# LED_PD_AB_WH_3000149.net
KiCad netlist of a schematic drawn in Altium Designer
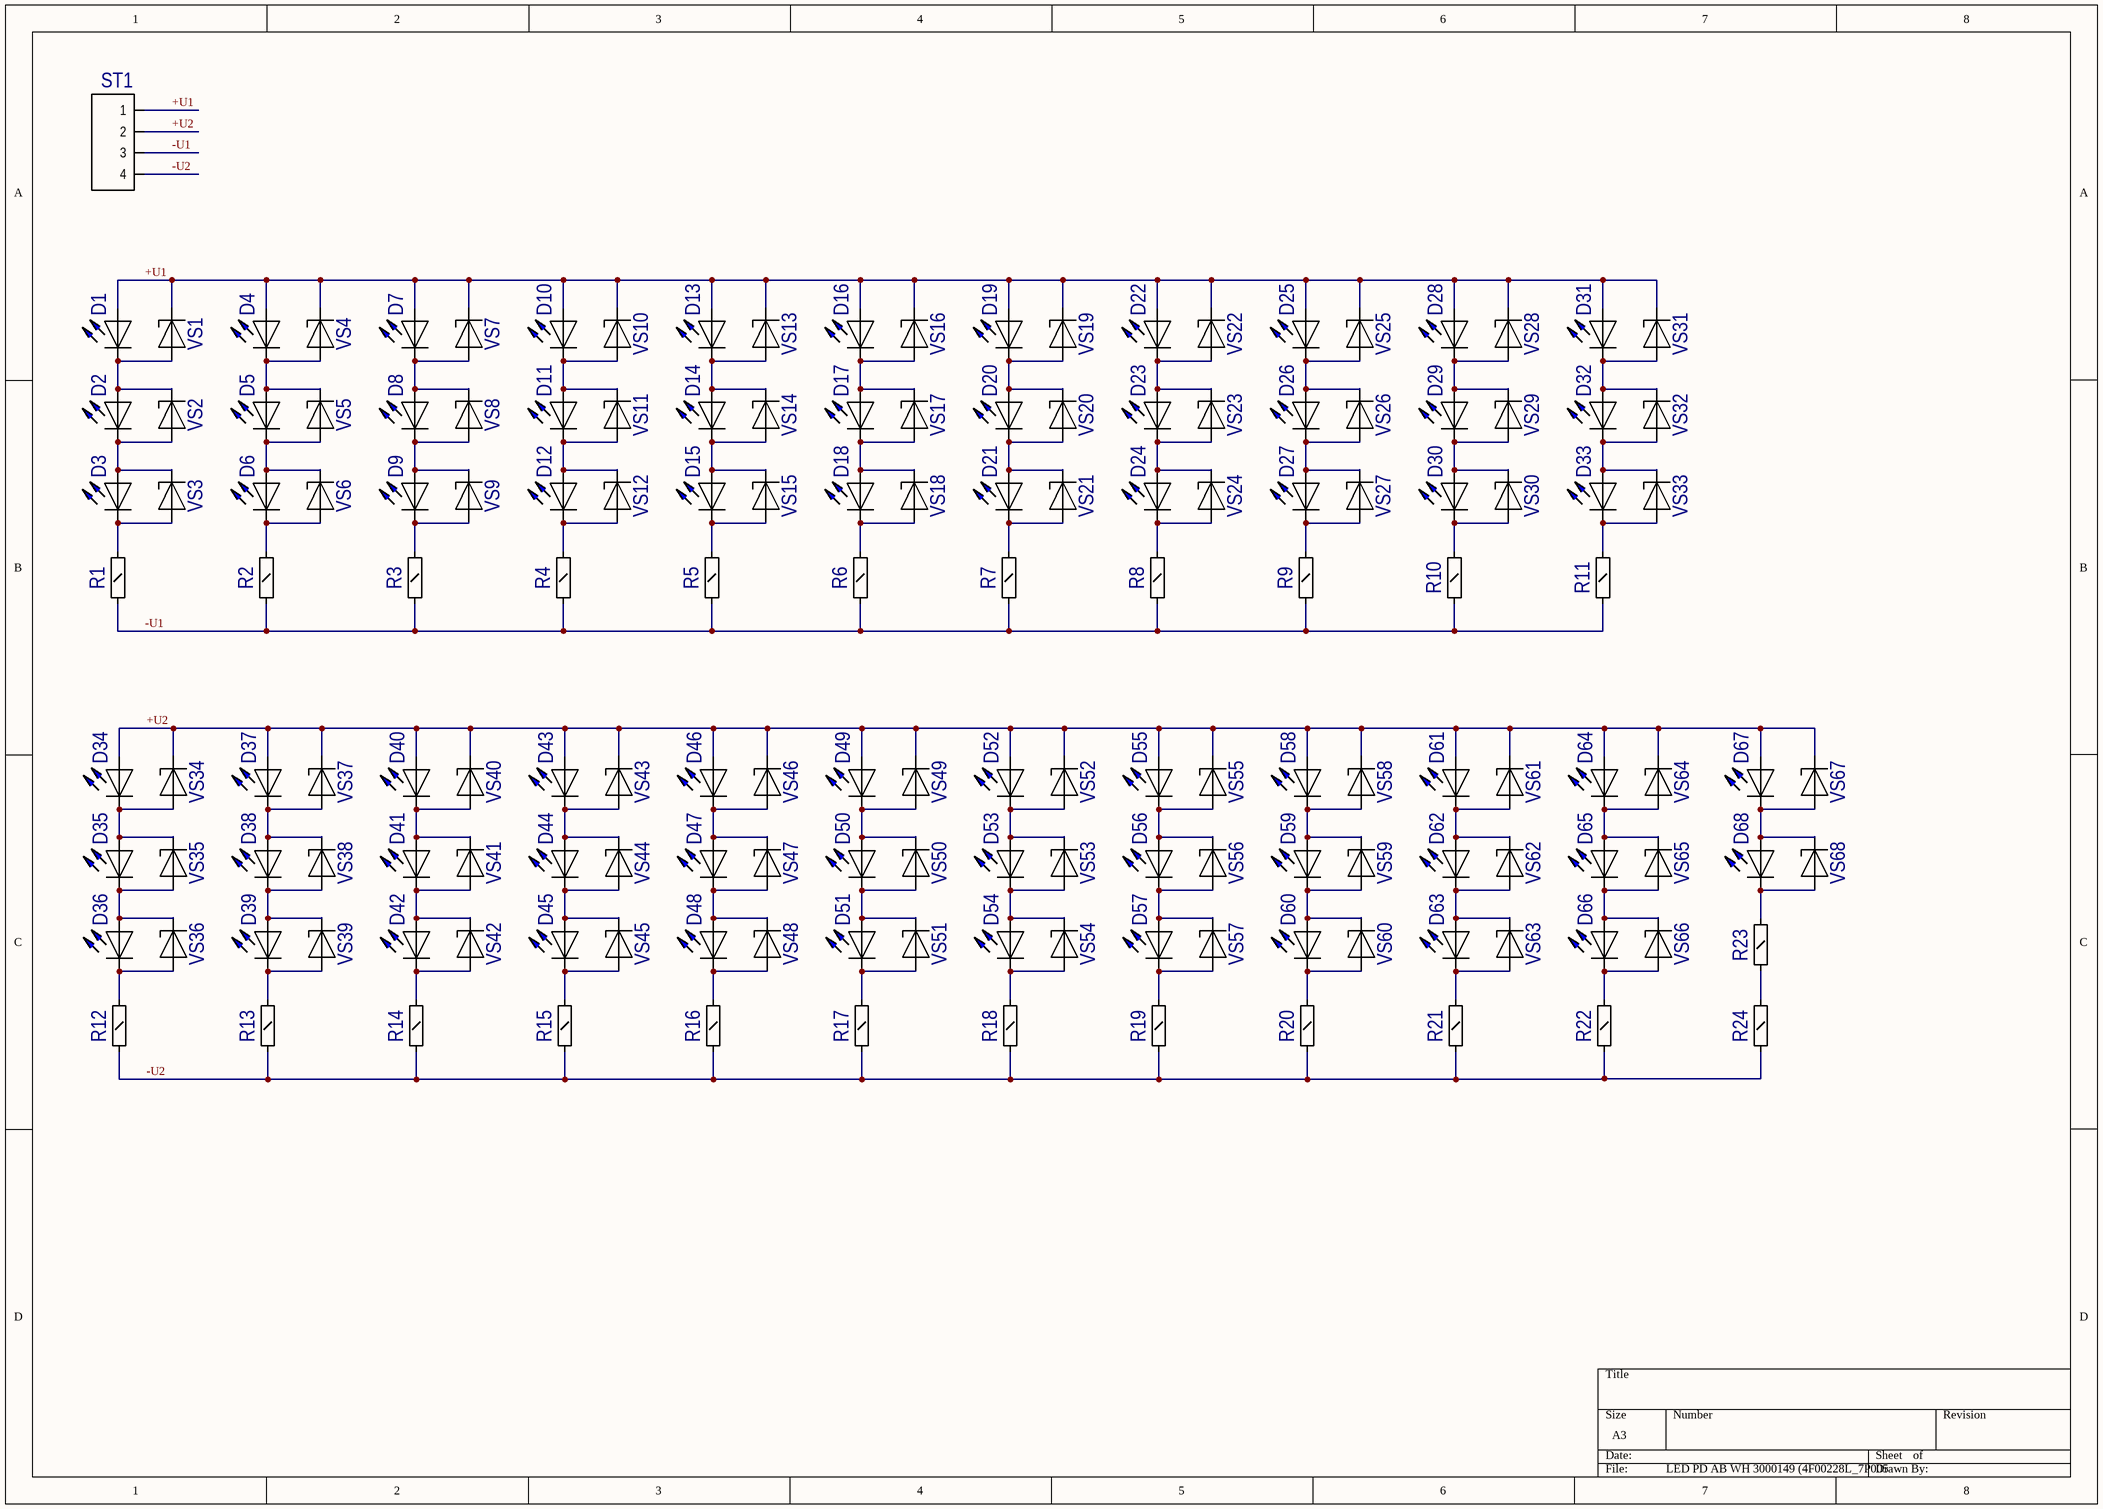
[diagram p0: LED PD AB WH 3000149 (4F00228L_7P00501A)_sch.SchDoc]

(export (version "E")
  (design (tool "Eeschema 10.0.6"))
  (components
    (comp (ref "D1")
      (value "LT_T66G")
      (footprint "T66G")
      (description "{Description}")
      (libsource (lib "LED PD GTL WH 3000148 (4F00222L_7P00492A)") (part "LT_T66G"))
    )
    (comp (ref "D2")
      (value "LT_T66G")
      (footprint "T66G")
      (description "{Description}")
      (libsource (lib "LED PD GTL WH 3000148 (4F00222L_7P00492A)") (part "LT_T66G"))
    )
    (comp (ref "D3")
      (value "LT_T66G")
      (footprint "T66G")
      (description "{Description}")
      (libsource (lib "LED PD GTL WH 3000148 (4F00222L_7P00492A)") (part "LT_T66G"))
    )
    (comp (ref "D4")
      (value "LT_T66G")
      (footprint "T66G")
      (description "{Description}")
      (libsource (lib "LED PD GTL WH 3000148 (4F00222L_7P00492A)") (part "LT_T66G"))
    )
    (comp (ref "D5")
      (value "LT_T66G")
      (footprint "T66G")
      (description "{Description}")
      (libsource (lib "LED PD GTL WH 3000148 (4F00222L_7P00492A)") (part "LT_T66G"))
    )
    (comp (ref "D6")
      (value "LT_T66G")
      (footprint "T66G")
      (description "{Description}")
      (libsource (lib "LED PD GTL WH 3000148 (4F00222L_7P00492A)") (part "LT_T66G"))
    )
    (comp (ref "D7")
      (value "LT_T66G")
      (footprint "T66G")
      (description "{Description}")
      (libsource (lib "LED PD GTL WH 3000148 (4F00222L_7P00492A)") (part "LT_T66G"))
    )
    (comp (ref "D8")
      (value "LT_T66G")
      (footprint "T66G")
      (description "{Description}")
      (libsource (lib "LED PD GTL WH 3000148 (4F00222L_7P00492A)") (part "LT_T66G"))
    )
    (comp (ref "D9")
      (value "LT_T66G")
      (footprint "T66G")
      (description "{Description}")
      (libsource (lib "LED PD GTL WH 3000148 (4F00222L_7P00492A)") (part "LT_T66G"))
    )
    (comp (ref "D10")
      (value "LT_T66G")
      (footprint "T66G")
      (description "{Description}")
      (libsource (lib "LED PD GTL WH 3000148 (4F00222L_7P00492A)") (part "LT_T66G"))
    )
    (comp (ref "D11")
      (value "LT_T66G")
      (footprint "T66G")
      (description "{Description}")
      (libsource (lib "LED PD GTL WH 3000148 (4F00222L_7P00492A)") (part "LT_T66G"))
    )
    (comp (ref "D12")
      (value "LT_T66G")
      (footprint "T66G")
      (description "{Description}")
      (libsource (lib "LED PD GTL WH 3000148 (4F00222L_7P00492A)") (part "LT_T66G"))
    )
    (comp (ref "D13")
      (value "LT_T66G")
      (footprint "T66G")
      (description "{Description}")
      (libsource (lib "LED PD GTL WH 3000148 (4F00222L_7P00492A)") (part "LT_T66G"))
    )
    (comp (ref "D14")
      (value "LT_T66G")
      (footprint "T66G")
      (description "{Description}")
      (libsource (lib "LED PD GTL WH 3000148 (4F00222L_7P00492A)") (part "LT_T66G"))
    )
    (comp (ref "D15")
      (value "LT_T66G")
      (footprint "T66G")
      (description "{Description}")
      (libsource (lib "LED PD GTL WH 3000148 (4F00222L_7P00492A)") (part "LT_T66G"))
    )
    (comp (ref "D16")
      (value "LT_T66G")
      (footprint "T66G")
      (description "{Description}")
      (libsource (lib "LED PD GTL WH 3000148 (4F00222L_7P00492A)") (part "LT_T66G"))
    )
    (comp (ref "D17")
      (value "LT_T66G")
      (footprint "T66G")
      (description "{Description}")
      (libsource (lib "LED PD GTL WH 3000148 (4F00222L_7P00492A)") (part "LT_T66G"))
    )
    (comp (ref "D18")
      (value "LT_T66G")
      (footprint "T66G")
      (description "{Description}")
      (libsource (lib "LED PD GTL WH 3000148 (4F00222L_7P00492A)") (part "LT_T66G"))
    )
    (comp (ref "D19")
      (value "LT_T66G")
      (footprint "T66G")
      (description "{Description}")
      (libsource (lib "LED PD GTL WH 3000148 (4F00222L_7P00492A)") (part "LT_T66G"))
    )
    (comp (ref "D20")
      (value "LT_T66G")
      (footprint "T66G")
      (description "{Description}")
      (libsource (lib "LED PD GTL WH 3000148 (4F00222L_7P00492A)") (part "LT_T66G"))
    )
    (comp (ref "D21")
      (value "LT_T66G")
      (footprint "T66G")
      (description "{Description}")
      (libsource (lib "LED PD GTL WH 3000148 (4F00222L_7P00492A)") (part "LT_T66G"))
    )
    (comp (ref "D22")
      (value "LT_T66G")
      (footprint "T66G")
      (description "{Description}")
      (libsource (lib "LED PD GTL WH 3000148 (4F00222L_7P00492A)") (part "LT_T66G"))
    )
    (comp (ref "D23")
      (value "LT_T66G")
      (footprint "T66G")
      (description "{Description}")
      (libsource (lib "LED PD GTL WH 3000148 (4F00222L_7P00492A)") (part "LT_T66G"))
    )
    (comp (ref "D24")
      (value "LT_T66G")
      (footprint "T66G")
      (description "{Description}")
      (libsource (lib "LED PD GTL WH 3000148 (4F00222L_7P00492A)") (part "LT_T66G"))
    )
    (comp (ref "D25")
      (value "LT_T66G")
      (footprint "T66G")
      (description "{Description}")
      (libsource (lib "LED PD GTL WH 3000148 (4F00222L_7P00492A)") (part "LT_T66G"))
    )
    (comp (ref "D26")
      (value "LT_T66G")
      (footprint "T66G")
      (description "{Description}")
      (libsource (lib "LED PD GTL WH 3000148 (4F00222L_7P00492A)") (part "LT_T66G"))
    )
    (comp (ref "D27")
      (value "LT_T66G")
      (footprint "T66G")
      (description "{Description}")
      (libsource (lib "LED PD GTL WH 3000148 (4F00222L_7P00492A)") (part "LT_T66G"))
    )
    (comp (ref "D28")
      (value "LT_T66G")
      (footprint "T66G")
      (description "{Description}")
      (libsource (lib "LED PD GTL WH 3000148 (4F00222L_7P00492A)") (part "LT_T66G"))
    )
    (comp (ref "D29")
      (value "LT_T66G")
      (footprint "T66G")
      (description "{Description}")
      (libsource (lib "LED PD GTL WH 3000148 (4F00222L_7P00492A)") (part "LT_T66G"))
    )
    (comp (ref "D30")
      (value "LT_T66G")
      (footprint "T66G")
      (description "{Description}")
      (libsource (lib "LED PD GTL WH 3000148 (4F00222L_7P00492A)") (part "LT_T66G"))
    )
    (comp (ref "D31")
      (value "LT_T66G")
      (footprint "T66G")
      (description "{Description}")
      (libsource (lib "LED PD GTL WH 3000148 (4F00222L_7P00492A)") (part "LT_T66G"))
    )
    (comp (ref "D32")
      (value "LT_T66G")
      (footprint "T66G")
      (description "{Description}")
      (libsource (lib "LED PD GTL WH 3000148 (4F00222L_7P00492A)") (part "LT_T66G"))
    )
    (comp (ref "D33")
      (value "LT_T66G")
      (footprint "T66G")
      (description "{Description}")
      (libsource (lib "LED PD GTL WH 3000148 (4F00222L_7P00492A)") (part "LT_T66G"))
    )
    (comp (ref "D34")
      (value "LT_T66G")
      (footprint "T66G")
      (description "{Description}")
      (libsource (lib "LED PD GTL WH 3000148 (4F00222L_7P00492A)") (part "LT_T66G"))
    )
    (comp (ref "D35")
      (value "LT_T66G")
      (footprint "T66G")
      (description "{Description}")
      (libsource (lib "LED PD GTL WH 3000148 (4F00222L_7P00492A)") (part "LT_T66G"))
    )
    (comp (ref "D36")
      (value "LT_T66G")
      (footprint "T66G")
      (description "{Description}")
      (libsource (lib "LED PD GTL WH 3000148 (4F00222L_7P00492A)") (part "LT_T66G"))
    )
    (comp (ref "D37")
      (value "LT_T66G")
      (footprint "T66G")
      (description "{Description}")
      (libsource (lib "LED PD GTL WH 3000148 (4F00222L_7P00492A)") (part "LT_T66G"))
    )
    (comp (ref "D38")
      (value "LT_T66G")
      (footprint "T66G")
      (description "{Description}")
      (libsource (lib "LED PD GTL WH 3000148 (4F00222L_7P00492A)") (part "LT_T66G"))
    )
    (comp (ref "D39")
      (value "LT_T66G")
      (footprint "T66G")
      (description "{Description}")
      (libsource (lib "LED PD GTL WH 3000148 (4F00222L_7P00492A)") (part "LT_T66G"))
    )
    (comp (ref "D40")
      (value "LT_T66G")
      (footprint "T66G")
      (description "{Description}")
      (libsource (lib "LED PD GTL WH 3000148 (4F00222L_7P00492A)") (part "LT_T66G"))
    )
    (comp (ref "D41")
      (value "LT_T66G")
      (footprint "T66G")
      (description "{Description}")
      (libsource (lib "LED PD GTL WH 3000148 (4F00222L_7P00492A)") (part "LT_T66G"))
    )
    (comp (ref "D42")
      (value "LT_T66G")
      (footprint "T66G")
      (description "{Description}")
      (libsource (lib "LED PD GTL WH 3000148 (4F00222L_7P00492A)") (part "LT_T66G"))
    )
    (comp (ref "D43")
      (value "LT_T66G")
      (footprint "T66G")
      (description "{Description}")
      (libsource (lib "LED PD GTL WH 3000148 (4F00222L_7P00492A)") (part "LT_T66G"))
    )
    (comp (ref "D44")
      (value "LT_T66G")
      (footprint "T66G")
      (description "{Description}")
      (libsource (lib "LED PD GTL WH 3000148 (4F00222L_7P00492A)") (part "LT_T66G"))
    )
    (comp (ref "D45")
      (value "LT_T66G")
      (footprint "T66G")
      (description "{Description}")
      (libsource (lib "LED PD GTL WH 3000148 (4F00222L_7P00492A)") (part "LT_T66G"))
    )
    (comp (ref "D46")
      (value "LT_T66G")
      (footprint "T66G")
      (description "{Description}")
      (libsource (lib "LED PD GTL WH 3000148 (4F00222L_7P00492A)") (part "LT_T66G"))
    )
    (comp (ref "D47")
      (value "LT_T66G")
      (footprint "T66G")
      (description "{Description}")
      (libsource (lib "LED PD GTL WH 3000148 (4F00222L_7P00492A)") (part "LT_T66G"))
    )
    (comp (ref "D48")
      (value "LT_T66G")
      (footprint "T66G")
      (description "{Description}")
      (libsource (lib "LED PD GTL WH 3000148 (4F00222L_7P00492A)") (part "LT_T66G"))
    )
    (comp (ref "D49")
      (value "LT_T66G")
      (footprint "T66G")
      (description "{Description}")
      (libsource (lib "LED PD GTL WH 3000148 (4F00222L_7P00492A)") (part "LT_T66G"))
    )
    (comp (ref "D50")
      (value "LT_T66G")
      (footprint "T66G")
      (description "{Description}")
      (libsource (lib "LED PD GTL WH 3000148 (4F00222L_7P00492A)") (part "LT_T66G"))
    )
    (comp (ref "D51")
      (value "LT_T66G")
      (footprint "T66G")
      (description "{Description}")
      (libsource (lib "LED PD GTL WH 3000148 (4F00222L_7P00492A)") (part "LT_T66G"))
    )
    (comp (ref "D52")
      (value "LT_T66G")
      (footprint "T66G")
      (description "{Description}")
      (libsource (lib "LED PD GTL WH 3000148 (4F00222L_7P00492A)") (part "LT_T66G"))
    )
    (comp (ref "D53")
      (value "LT_T66G")
      (footprint "T66G")
      (description "{Description}")
      (libsource (lib "LED PD GTL WH 3000148 (4F00222L_7P00492A)") (part "LT_T66G"))
    )
    (comp (ref "D54")
      (value "LT_T66G")
      (footprint "T66G")
      (description "{Description}")
      (libsource (lib "LED PD GTL WH 3000148 (4F00222L_7P00492A)") (part "LT_T66G"))
    )
    (comp (ref "D55")
      (value "LT_T66G")
      (footprint "T66G")
      (description "{Description}")
      (libsource (lib "LED PD GTL WH 3000148 (4F00222L_7P00492A)") (part "LT_T66G"))
    )
    (comp (ref "D56")
      (value "LT_T66G")
      (footprint "T66G")
      (description "{Description}")
      (libsource (lib "LED PD GTL WH 3000148 (4F00222L_7P00492A)") (part "LT_T66G"))
    )
    (comp (ref "D57")
      (value "LT_T66G")
      (footprint "T66G")
      (description "{Description}")
      (libsource (lib "LED PD GTL WH 3000148 (4F00222L_7P00492A)") (part "LT_T66G"))
    )
    (comp (ref "D58")
      (value "LT_T66G")
      (footprint "T66G")
      (description "{Description}")
      (libsource (lib "LED PD GTL WH 3000148 (4F00222L_7P00492A)") (part "LT_T66G"))
    )
    (comp (ref "D59")
      (value "LT_T66G")
      (footprint "T66G")
      (description "{Description}")
      (libsource (lib "LED PD GTL WH 3000148 (4F00222L_7P00492A)") (part "LT_T66G"))
    )
    (comp (ref "D60")
      (value "LT_T66G")
      (footprint "T66G")
      (description "{Description}")
      (libsource (lib "LED PD GTL WH 3000148 (4F00222L_7P00492A)") (part "LT_T66G"))
    )
    (comp (ref "D61")
      (value "LT_T66G")
      (footprint "T66G")
      (description "{Description}")
      (libsource (lib "LED PD GTL WH 3000148 (4F00222L_7P00492A)") (part "LT_T66G"))
    )
    (comp (ref "D62")
      (value "LT_T66G")
      (footprint "T66G")
      (description "{Description}")
      (libsource (lib "LED PD GTL WH 3000148 (4F00222L_7P00492A)") (part "LT_T66G"))
    )
    (comp (ref "D63")
      (value "LT_T66G")
      (footprint "T66G")
      (description "{Description}")
      (libsource (lib "LED PD GTL WH 3000148 (4F00222L_7P00492A)") (part "LT_T66G"))
    )
    (comp (ref "D64")
      (value "LT_T66G")
      (footprint "T66G")
      (description "{Description}")
      (libsource (lib "LED PD GTL WH 3000148 (4F00222L_7P00492A)") (part "LT_T66G"))
    )
    (comp (ref "D65")
      (value "LT_T66G")
      (footprint "T66G")
      (description "{Description}")
      (libsource (lib "LED PD GTL WH 3000148 (4F00222L_7P00492A)") (part "LT_T66G"))
    )
    (comp (ref "D66")
      (value "LT_T66G")
      (footprint "T66G")
      (description "{Description}")
      (libsource (lib "LED PD GTL WH 3000148 (4F00222L_7P00492A)") (part "LT_T66G"))
    )
    (comp (ref "D67")
      (value "LT_T66G")
      (footprint "T66G")
      (description "{Description}")
      (libsource (lib "LED PD GTL WH 3000148 (4F00222L_7P00492A)") (part "LT_T66G"))
    )
    (comp (ref "D68")
      (value "LT_T66G")
      (footprint "T66G")
      (description "{Description}")
      (libsource (lib "LED PD GTL WH 3000148 (4F00222L_7P00492A)") (part "LT_T66G"))
    )
    (comp (ref "R1")
      (value "R1206S")
      (footprint "RC1206S")
      (libsource (lib "LED PD GTL WH 3000148 (4F00222L_7P00492A)") (part "R1206S"))
    )
    (comp (ref "R2")
      (value "R1206S")
      (footprint "RC1206S")
      (libsource (lib "LED PD GTL WH 3000148 (4F00222L_7P00492A)") (part "R1206S"))
    )
    (comp (ref "R3")
      (value "R1206S")
      (footprint "RC1206S")
      (libsource (lib "LED PD GTL WH 3000148 (4F00222L_7P00492A)") (part "R1206S"))
    )
    (comp (ref "R4")
      (value "R1206S")
      (footprint "RC1206S")
      (libsource (lib "LED PD GTL WH 3000148 (4F00222L_7P00492A)") (part "R1206S"))
    )
    (comp (ref "R5")
      (value "R1206S")
      (footprint "RC1206S")
      (libsource (lib "LED PD GTL WH 3000148 (4F00222L_7P00492A)") (part "R1206S"))
    )
    (comp (ref "R6")
      (value "R1206S")
      (footprint "RC1206S")
      (libsource (lib "LED PD GTL WH 3000148 (4F00222L_7P00492A)") (part "R1206S"))
    )
    (comp (ref "R7")
      (value "R1206S")
      (footprint "RC1206S")
      (libsource (lib "LED PD GTL WH 3000148 (4F00222L_7P00492A)") (part "R1206S"))
    )
    (comp (ref "R8")
      (value "R1206S")
      (footprint "RC1206S")
      (libsource (lib "LED PD GTL WH 3000148 (4F00222L_7P00492A)") (part "R1206S"))
    )
    (comp (ref "R9")
      (value "R1206S")
      (footprint "RC1206S")
      (libsource (lib "LED PD GTL WH 3000148 (4F00222L_7P00492A)") (part "R1206S"))
    )
    (comp (ref "R10")
      (value "R1206S")
      (footprint "RC1206S")
      (libsource (lib "LED PD GTL WH 3000148 (4F00222L_7P00492A)") (part "R1206S"))
    )
    (comp (ref "R11")
      (value "R1206S")
      (footprint "RC1206S")
      (libsource (lib "LED PD GTL WH 3000148 (4F00222L_7P00492A)") (part "R1206S"))
    )
    (comp (ref "R12")
      (value "R1206S")
      (footprint "RC1206S")
      (libsource (lib "LED PD GTL WH 3000148 (4F00222L_7P00492A)") (part "R1206S"))
    )
    (comp (ref "R13")
      (value "R1206S")
      (footprint "RC1206S")
      (libsource (lib "LED PD GTL WH 3000148 (4F00222L_7P00492A)") (part "R1206S"))
    )
    (comp (ref "R14")
      (value "R1206S")
      (footprint "RC1206S")
      (libsource (lib "LED PD GTL WH 3000148 (4F00222L_7P00492A)") (part "R1206S"))
    )
    (comp (ref "R15")
      (value "R1206S")
      (footprint "RC1206S")
      (libsource (lib "LED PD GTL WH 3000148 (4F00222L_7P00492A)") (part "R1206S"))
    )
    (comp (ref "R16")
      (value "R1206S")
      (footprint "RC1206S")
      (libsource (lib "LED PD GTL WH 3000148 (4F00222L_7P00492A)") (part "R1206S"))
    )
    (comp (ref "R17")
      (value "R1206S")
      (footprint "RC1206S")
      (libsource (lib "LED PD GTL WH 3000148 (4F00222L_7P00492A)") (part "R1206S"))
    )
    (comp (ref "R18")
      (value "R1206S")
      (footprint "RC1206S")
      (libsource (lib "LED PD GTL WH 3000148 (4F00222L_7P00492A)") (part "R1206S"))
    )
    (comp (ref "R19")
      (value "R1206S")
      (footprint "RC1206S")
      (libsource (lib "LED PD GTL WH 3000148 (4F00222L_7P00492A)") (part "R1206S"))
    )
    (comp (ref "R20")
      (value "R1206S")
      (footprint "RC1206S")
      (libsource (lib "LED PD GTL WH 3000148 (4F00222L_7P00492A)") (part "R1206S"))
    )
    (comp (ref "R21")
      (value "R1206S")
      (footprint "RC1206S")
      (libsource (lib "LED PD GTL WH 3000148 (4F00222L_7P00492A)") (part "R1206S"))
    )
    (comp (ref "R22")
      (value "R1206S")
      (footprint "RC1206S")
      (libsource (lib "LED PD GTL WH 3000148 (4F00222L_7P00492A)") (part "R1206S"))
    )
    (comp (ref "R23")
      (value "R1206S")
      (footprint "RC1206S")
      (libsource (lib "LED PD GTL WH 3000148 (4F00222L_7P00492A)") (part "R1206S"))
    )
    (comp (ref "R24")
      (value "R1206S")
      (footprint "RC1206S")
      (libsource (lib "LED PD GTL WH 3000148 (4F00222L_7P00492A)") (part "R1206S"))
    )
    (comp (ref "ST1")
      (value "BAND4")
      (footprint "BAND4")
      (libsource (lib "LED PD GTL WH 3000148 (4F00222L_7P00492A)") (part "BAND4"))
    )
    (comp (ref "VS1")
      (value "BZX84")
      (footprint "SOT23")
      (libsource (lib "LED PD GTL WH 3000148 (4F00222L_7P00492A)") (part "BZX84"))
    )
    (comp (ref "VS2")
      (value "BZX84")
      (footprint "SOT23")
      (libsource (lib "LED PD GTL WH 3000148 (4F00222L_7P00492A)") (part "BZX84"))
    )
    (comp (ref "VS3")
      (value "BZX84")
      (footprint "SOT23")
      (libsource (lib "LED PD GTL WH 3000148 (4F00222L_7P00492A)") (part "BZX84"))
    )
    (comp (ref "VS4")
      (value "BZX84")
      (footprint "SOT23")
      (libsource (lib "LED PD GTL WH 3000148 (4F00222L_7P00492A)") (part "BZX84"))
    )
    (comp (ref "VS5")
      (value "BZX84")
      (footprint "SOT23")
      (libsource (lib "LED PD GTL WH 3000148 (4F00222L_7P00492A)") (part "BZX84"))
    )
    (comp (ref "VS6")
      (value "BZX84")
      (footprint "SOT23")
      (libsource (lib "LED PD GTL WH 3000148 (4F00222L_7P00492A)") (part "BZX84"))
    )
    (comp (ref "VS7")
      (value "BZX84")
      (footprint "SOT23")
      (libsource (lib "LED PD GTL WH 3000148 (4F00222L_7P00492A)") (part "BZX84"))
    )
    (comp (ref "VS8")
      (value "BZX84")
      (footprint "SOT23")
      (libsource (lib "LED PD GTL WH 3000148 (4F00222L_7P00492A)") (part "BZX84"))
    )
    (comp (ref "VS9")
      (value "BZX84")
      (footprint "SOT23")
      (libsource (lib "LED PD GTL WH 3000148 (4F00222L_7P00492A)") (part "BZX84"))
    )
    (comp (ref "VS10")
      (value "BZX84")
      (footprint "SOT23")
      (libsource (lib "LED PD GTL WH 3000148 (4F00222L_7P00492A)") (part "BZX84"))
    )
    (comp (ref "VS11")
      (value "BZX84")
      (footprint "SOT23")
      (libsource (lib "LED PD GTL WH 3000148 (4F00222L_7P00492A)") (part "BZX84"))
    )
    (comp (ref "VS12")
      (value "BZX84")
      (footprint "SOT23")
      (libsource (lib "LED PD GTL WH 3000148 (4F00222L_7P00492A)") (part "BZX84"))
    )
    (comp (ref "VS13")
      (value "BZX84")
      (footprint "SOT23")
      (libsource (lib "LED PD GTL WH 3000148 (4F00222L_7P00492A)") (part "BZX84"))
    )
    (comp (ref "VS14")
      (value "BZX84")
      (footprint "SOT23")
      (libsource (lib "LED PD GTL WH 3000148 (4F00222L_7P00492A)") (part "BZX84"))
    )
    (comp (ref "VS15")
      (value "BZX84")
      (footprint "SOT23")
      (libsource (lib "LED PD GTL WH 3000148 (4F00222L_7P00492A)") (part "BZX84"))
    )
    (comp (ref "VS16")
      (value "BZX84")
      (footprint "SOT23")
      (libsource (lib "LED PD GTL WH 3000148 (4F00222L_7P00492A)") (part "BZX84"))
    )
    (comp (ref "VS17")
      (value "BZX84")
      (footprint "SOT23")
      (libsource (lib "LED PD GTL WH 3000148 (4F00222L_7P00492A)") (part "BZX84"))
    )
    (comp (ref "VS18")
      (value "BZX84")
      (footprint "SOT23")
      (libsource (lib "LED PD GTL WH 3000148 (4F00222L_7P00492A)") (part "BZX84"))
    )
    (comp (ref "VS19")
      (value "BZX84")
      (footprint "SOT23")
      (libsource (lib "LED PD GTL WH 3000148 (4F00222L_7P00492A)") (part "BZX84"))
    )
    (comp (ref "VS20")
      (value "BZX84")
      (footprint "SOT23")
      (libsource (lib "LED PD GTL WH 3000148 (4F00222L_7P00492A)") (part "BZX84"))
    )
    (comp (ref "VS21")
      (value "BZX84")
      (footprint "SOT23")
      (libsource (lib "LED PD GTL WH 3000148 (4F00222L_7P00492A)") (part "BZX84"))
    )
    (comp (ref "VS22")
      (value "BZX84")
      (footprint "SOT23")
      (libsource (lib "LED PD GTL WH 3000148 (4F00222L_7P00492A)") (part "BZX84"))
    )
    (comp (ref "VS23")
      (value "BZX84")
      (footprint "SOT23")
      (libsource (lib "LED PD GTL WH 3000148 (4F00222L_7P00492A)") (part "BZX84"))
    )
    (comp (ref "VS24")
      (value "BZX84")
      (footprint "SOT23")
      (libsource (lib "LED PD GTL WH 3000148 (4F00222L_7P00492A)") (part "BZX84"))
    )
    (comp (ref "VS25")
      (value "BZX84")
      (footprint "SOT23")
      (libsource (lib "LED PD GTL WH 3000148 (4F00222L_7P00492A)") (part "BZX84"))
    )
    (comp (ref "VS26")
      (value "BZX84")
      (footprint "SOT23")
      (libsource (lib "LED PD GTL WH 3000148 (4F00222L_7P00492A)") (part "BZX84"))
    )
    (comp (ref "VS27")
      (value "BZX84")
      (footprint "SOT23")
      (libsource (lib "LED PD GTL WH 3000148 (4F00222L_7P00492A)") (part "BZX84"))
    )
    (comp (ref "VS28")
      (value "BZX84")
      (footprint "SOT23")
      (libsource (lib "LED PD GTL WH 3000148 (4F00222L_7P00492A)") (part "BZX84"))
    )
    (comp (ref "VS29")
      (value "BZX84")
      (footprint "SOT23")
      (libsource (lib "LED PD GTL WH 3000148 (4F00222L_7P00492A)") (part "BZX84"))
    )
    (comp (ref "VS30")
      (value "BZX84")
      (footprint "SOT23")
      (libsource (lib "LED PD GTL WH 3000148 (4F00222L_7P00492A)") (part "BZX84"))
    )
    (comp (ref "VS31")
      (value "BZX84")
      (footprint "SOT23")
      (libsource (lib "LED PD GTL WH 3000148 (4F00222L_7P00492A)") (part "BZX84"))
    )
    (comp (ref "VS32")
      (value "BZX84")
      (footprint "SOT23")
      (libsource (lib "LED PD GTL WH 3000148 (4F00222L_7P00492A)") (part "BZX84"))
    )
    (comp (ref "VS33")
      (value "BZX84")
      (footprint "SOT23")
      (libsource (lib "LED PD GTL WH 3000148 (4F00222L_7P00492A)") (part "BZX84"))
    )
    (comp (ref "VS34")
      (value "BZX84")
      (footprint "SOT23")
      (libsource (lib "LED PD GTL WH 3000148 (4F00222L_7P00492A)") (part "BZX84"))
    )
    (comp (ref "VS35")
      (value "BZX84")
      (footprint "SOT23")
      (libsource (lib "LED PD GTL WH 3000148 (4F00222L_7P00492A)") (part "BZX84"))
    )
    (comp (ref "VS36")
      (value "BZX84")
      (footprint "SOT23")
      (libsource (lib "LED PD GTL WH 3000148 (4F00222L_7P00492A)") (part "BZX84"))
    )
    (comp (ref "VS37")
      (value "BZX84")
      (footprint "SOT23")
      (libsource (lib "LED PD GTL WH 3000148 (4F00222L_7P00492A)") (part "BZX84"))
    )
    (comp (ref "VS38")
      (value "BZX84")
      (footprint "SOT23")
      (libsource (lib "LED PD GTL WH 3000148 (4F00222L_7P00492A)") (part "BZX84"))
    )
    (comp (ref "VS39")
      (value "BZX84")
      (footprint "SOT23")
      (libsource (lib "LED PD GTL WH 3000148 (4F00222L_7P00492A)") (part "BZX84"))
    )
    (comp (ref "VS40")
      (value "BZX84")
      (footprint "SOT23")
      (libsource (lib "LED PD GTL WH 3000148 (4F00222L_7P00492A)") (part "BZX84"))
    )
    (comp (ref "VS41")
      (value "BZX84")
      (footprint "SOT23")
      (libsource (lib "LED PD GTL WH 3000148 (4F00222L_7P00492A)") (part "BZX84"))
    )
    (comp (ref "VS42")
      (value "BZX84")
      (footprint "SOT23")
      (libsource (lib "LED PD GTL WH 3000148 (4F00222L_7P00492A)") (part "BZX84"))
    )
    (comp (ref "VS43")
      (value "BZX84")
      (footprint "SOT23")
      (libsource (lib "LED PD GTL WH 3000148 (4F00222L_7P00492A)") (part "BZX84"))
    )
    (comp (ref "VS44")
      (value "BZX84")
      (footprint "SOT23")
      (libsource (lib "LED PD GTL WH 3000148 (4F00222L_7P00492A)") (part "BZX84"))
    )
    (comp (ref "VS45")
      (value "BZX84")
      (footprint "SOT23")
      (libsource (lib "LED PD GTL WH 3000148 (4F00222L_7P00492A)") (part "BZX84"))
    )
    (comp (ref "VS46")
      (value "BZX84")
      (footprint "SOT23")
      (libsource (lib "LED PD GTL WH 3000148 (4F00222L_7P00492A)") (part "BZX84"))
    )
    (comp (ref "VS47")
      (value "BZX84")
      (footprint "SOT23")
      (libsource (lib "LED PD GTL WH 3000148 (4F00222L_7P00492A)") (part "BZX84"))
    )
    (comp (ref "VS48")
      (value "BZX84")
      (footprint "SOT23")
      (libsource (lib "LED PD GTL WH 3000148 (4F00222L_7P00492A)") (part "BZX84"))
    )
    (comp (ref "VS49")
      (value "BZX84")
      (footprint "SOT23")
      (libsource (lib "LED PD GTL WH 3000148 (4F00222L_7P00492A)") (part "BZX84"))
    )
    (comp (ref "VS50")
      (value "BZX84")
      (footprint "SOT23")
      (libsource (lib "LED PD GTL WH 3000148 (4F00222L_7P00492A)") (part "BZX84"))
    )
    (comp (ref "VS51")
      (value "BZX84")
      (footprint "SOT23")
      (libsource (lib "LED PD GTL WH 3000148 (4F00222L_7P00492A)") (part "BZX84"))
    )
    (comp (ref "VS52")
      (value "BZX84")
      (footprint "SOT23")
      (libsource (lib "LED PD GTL WH 3000148 (4F00222L_7P00492A)") (part "BZX84"))
    )
    (comp (ref "VS53")
      (value "BZX84")
      (footprint "SOT23")
      (libsource (lib "LED PD GTL WH 3000148 (4F00222L_7P00492A)") (part "BZX84"))
    )
    (comp (ref "VS54")
      (value "BZX84")
      (footprint "SOT23")
      (libsource (lib "LED PD GTL WH 3000148 (4F00222L_7P00492A)") (part "BZX84"))
    )
    (comp (ref "VS55")
      (value "BZX84")
      (footprint "SOT23")
      (libsource (lib "LED PD GTL WH 3000148 (4F00222L_7P00492A)") (part "BZX84"))
    )
    (comp (ref "VS56")
      (value "BZX84")
      (footprint "SOT23")
      (libsource (lib "LED PD GTL WH 3000148 (4F00222L_7P00492A)") (part "BZX84"))
    )
    (comp (ref "VS57")
      (value "BZX84")
      (footprint "SOT23")
      (libsource (lib "LED PD GTL WH 3000148 (4F00222L_7P00492A)") (part "BZX84"))
    )
    (comp (ref "VS58")
      (value "BZX84")
      (footprint "SOT23")
      (libsource (lib "LED PD GTL WH 3000148 (4F00222L_7P00492A)") (part "BZX84"))
    )
    (comp (ref "VS59")
      (value "BZX84")
      (footprint "SOT23")
      (libsource (lib "LED PD GTL WH 3000148 (4F00222L_7P00492A)") (part "BZX84"))
    )
    (comp (ref "VS60")
      (value "BZX84")
      (footprint "SOT23")
      (libsource (lib "LED PD GTL WH 3000148 (4F00222L_7P00492A)") (part "BZX84"))
    )
    (comp (ref "VS61")
      (value "BZX84")
      (footprint "SOT23")
      (libsource (lib "LED PD GTL WH 3000148 (4F00222L_7P00492A)") (part "BZX84"))
    )
    (comp (ref "VS62")
      (value "BZX84")
      (footprint "SOT23")
      (libsource (lib "LED PD GTL WH 3000148 (4F00222L_7P00492A)") (part "BZX84"))
    )
    (comp (ref "VS63")
      (value "BZX84")
      (footprint "SOT23")
      (libsource (lib "LED PD GTL WH 3000148 (4F00222L_7P00492A)") (part "BZX84"))
    )
    (comp (ref "VS64")
      (value "BZX84")
      (footprint "SOT23")
      (libsource (lib "LED PD GTL WH 3000148 (4F00222L_7P00492A)") (part "BZX84"))
    )
    (comp (ref "VS65")
      (value "BZX84")
      (footprint "SOT23")
      (libsource (lib "LED PD GTL WH 3000148 (4F00222L_7P00492A)") (part "BZX84"))
    )
    (comp (ref "VS66")
      (value "BZX84")
      (footprint "SOT23")
      (libsource (lib "LED PD GTL WH 3000148 (4F00222L_7P00492A)") (part "BZX84"))
    )
    (comp (ref "VS67")
      (value "BZX84")
      (footprint "SOT23")
      (libsource (lib "LED PD GTL WH 3000148 (4F00222L_7P00492A)") (part "BZX84"))
    )
    (comp (ref "VS68")
      (value "BZX84")
      (footprint "SOT23")
      (libsource (lib "LED PD GTL WH 3000148 (4F00222L_7P00492A)") (part "BZX84"))
    )
  )
  (nets
    (net (code "1") (name "/+U1") (class "Default")
      (node (ref "D1") (pin "2") (pintype "passive"))
      (node (ref "D10") (pin "2") (pintype "passive"))
      (node (ref "D13") (pin "2") (pintype "passive"))
      (node (ref "D16") (pin "2") (pintype "passive"))
      (node (ref "D19") (pin "2") (pintype "passive"))
      (node (ref "D22") (pin "2") (pintype "passive"))
      (node (ref "D25") (pin "2") (pintype "passive"))
      (node (ref "D28") (pin "2") (pintype "passive"))
      (node (ref "D31") (pin "2") (pintype "passive"))
      (node (ref "D4") (pin "2") (pintype "passive"))
      (node (ref "D7") (pin "2") (pintype "passive"))
      (node (ref "ST1") (pin "1") (pinfunction "1_1") (pintype "passive"))
      (node (ref "VS1") (pin "3") (pintype "passive"))
      (node (ref "VS10") (pin "3") (pintype "passive"))
      (node (ref "VS13") (pin "3") (pintype "passive"))
      (node (ref "VS16") (pin "3") (pintype "passive"))
      (node (ref "VS19") (pin "3") (pintype "passive"))
      (node (ref "VS22") (pin "3") (pintype "passive"))
      (node (ref "VS25") (pin "3") (pintype "passive"))
      (node (ref "VS28") (pin "3") (pintype "passive"))
      (node (ref "VS31") (pin "3") (pintype "passive"))
      (node (ref "VS4") (pin "3") (pintype "passive"))
      (node (ref "VS7") (pin "3") (pintype "passive"))
    )
    (net (code "2") (name "/+U2") (class "Default")
      (node (ref "D34") (pin "2") (pintype "passive"))
      (node (ref "D37") (pin "2") (pintype "passive"))
      (node (ref "D40") (pin "2") (pintype "passive"))
      (node (ref "D43") (pin "2") (pintype "passive"))
      (node (ref "D46") (pin "2") (pintype "passive"))
      (node (ref "D49") (pin "2") (pintype "passive"))
      (node (ref "D52") (pin "2") (pintype "passive"))
      (node (ref "D55") (pin "2") (pintype "passive"))
      (node (ref "D58") (pin "2") (pintype "passive"))
      (node (ref "D61") (pin "2") (pintype "passive"))
      (node (ref "D64") (pin "2") (pintype "passive"))
      (node (ref "D67") (pin "2") (pintype "passive"))
      (node (ref "ST1") (pin "2") (pinfunction "2_2") (pintype "passive"))
      (node (ref "VS34") (pin "3") (pintype "passive"))
      (node (ref "VS37") (pin "3") (pintype "passive"))
      (node (ref "VS40") (pin "3") (pintype "passive"))
      (node (ref "VS43") (pin "3") (pintype "passive"))
      (node (ref "VS46") (pin "3") (pintype "passive"))
      (node (ref "VS49") (pin "3") (pintype "passive"))
      (node (ref "VS52") (pin "3") (pintype "passive"))
      (node (ref "VS55") (pin "3") (pintype "passive"))
      (node (ref "VS58") (pin "3") (pintype "passive"))
      (node (ref "VS61") (pin "3") (pintype "passive"))
      (node (ref "VS64") (pin "3") (pintype "passive"))
      (node (ref "VS67") (pin "3") (pintype "passive"))
    )
    (net (code "3") (name "/-U1") (class "Default")
      (node (ref "R1") (pin "1") (pinfunction "1_1") (pintype "passive"))
      (node (ref "R10") (pin "1") (pinfunction "1_1") (pintype "passive"))
      (node (ref "R11") (pin "1") (pinfunction "1_1") (pintype "passive"))
      (node (ref "R2") (pin "1") (pinfunction "1_1") (pintype "passive"))
      (node (ref "R3") (pin "1") (pinfunction "1_1") (pintype "passive"))
      (node (ref "R4") (pin "1") (pinfunction "1_1") (pintype "passive"))
      (node (ref "R5") (pin "1") (pinfunction "1_1") (pintype "passive"))
      (node (ref "R6") (pin "1") (pinfunction "1_1") (pintype "passive"))
      (node (ref "R7") (pin "1") (pinfunction "1_1") (pintype "passive"))
      (node (ref "R8") (pin "1") (pinfunction "1_1") (pintype "passive"))
      (node (ref "R9") (pin "1") (pinfunction "1_1") (pintype "passive"))
      (node (ref "ST1") (pin "3") (pinfunction "3_3") (pintype "passive"))
    )
    (net (code "4") (name "/-U2") (class "Default")
      (node (ref "R12") (pin "1") (pinfunction "1_1") (pintype "passive"))
      (node (ref "R13") (pin "1") (pinfunction "1_1") (pintype "passive"))
      (node (ref "R14") (pin "1") (pinfunction "1_1") (pintype "passive"))
      (node (ref "R15") (pin "1") (pinfunction "1_1") (pintype "passive"))
      (node (ref "R16") (pin "1") (pinfunction "1_1") (pintype "passive"))
      (node (ref "R17") (pin "1") (pinfunction "1_1") (pintype "passive"))
      (node (ref "R18") (pin "1") (pinfunction "1_1") (pintype "passive"))
      (node (ref "R19") (pin "1") (pinfunction "1_1") (pintype "passive"))
      (node (ref "R20") (pin "1") (pinfunction "1_1") (pintype "passive"))
      (node (ref "R21") (pin "1") (pinfunction "1_1") (pintype "passive"))
      (node (ref "R22") (pin "1") (pinfunction "1_1") (pintype "passive"))
      (node (ref "R24") (pin "1") (pinfunction "1_1") (pintype "passive"))
      (node (ref "ST1") (pin "4") (pinfunction "4_4") (pintype "passive"))
    )
    (net (code "5") (name "Net-(D1-Pad1)") (class "Default")
      (node (ref "D1") (pin "1") (pintype "passive"))
      (node (ref "D2") (pin "2") (pintype "passive"))
      (node (ref "VS1") (pin "1") (pintype "passive"))
      (node (ref "VS2") (pin "3") (pintype "passive"))
    )
    (net (code "6") (name "Net-(D2-Pad1)") (class "Default")
      (node (ref "D2") (pin "1") (pintype "passive"))
      (node (ref "D3") (pin "2") (pintype "passive"))
      (node (ref "VS2") (pin "1") (pintype "passive"))
      (node (ref "VS3") (pin "3") (pintype "passive"))
    )
    (net (code "7") (name "Net-(D3-Pad1)") (class "Default")
      (node (ref "D3") (pin "1") (pintype "passive"))
      (node (ref "R1") (pin "2") (pinfunction "2_2") (pintype "passive"))
      (node (ref "VS3") (pin "1") (pintype "passive"))
    )
    (net (code "8") (name "Net-(D4-Pad1)") (class "Default")
      (node (ref "D4") (pin "1") (pintype "passive"))
      (node (ref "D5") (pin "2") (pintype "passive"))
      (node (ref "VS4") (pin "1") (pintype "passive"))
      (node (ref "VS5") (pin "3") (pintype "passive"))
    )
    (net (code "9") (name "Net-(D5-Pad1)") (class "Default")
      (node (ref "D5") (pin "1") (pintype "passive"))
      (node (ref "D6") (pin "2") (pintype "passive"))
      (node (ref "VS5") (pin "1") (pintype "passive"))
      (node (ref "VS6") (pin "3") (pintype "passive"))
    )
    (net (code "10") (name "Net-(D6-Pad1)") (class "Default")
      (node (ref "D6") (pin "1") (pintype "passive"))
      (node (ref "R2") (pin "2") (pinfunction "2_2") (pintype "passive"))
      (node (ref "VS6") (pin "1") (pintype "passive"))
    )
    (net (code "11") (name "Net-(D7-Pad1)") (class "Default")
      (node (ref "D7") (pin "1") (pintype "passive"))
      (node (ref "D8") (pin "2") (pintype "passive"))
      (node (ref "VS7") (pin "1") (pintype "passive"))
      (node (ref "VS8") (pin "3") (pintype "passive"))
    )
    (net (code "12") (name "Net-(D8-Pad1)") (class "Default")
      (node (ref "D8") (pin "1") (pintype "passive"))
      (node (ref "D9") (pin "2") (pintype "passive"))
      (node (ref "VS8") (pin "1") (pintype "passive"))
      (node (ref "VS9") (pin "3") (pintype "passive"))
    )
    (net (code "13") (name "Net-(D9-Pad1)") (class "Default")
      (node (ref "D9") (pin "1") (pintype "passive"))
      (node (ref "R3") (pin "2") (pinfunction "2_2") (pintype "passive"))
      (node (ref "VS9") (pin "1") (pintype "passive"))
    )
    (net (code "14") (name "Net-(D10-Pad1)") (class "Default")
      (node (ref "D10") (pin "1") (pintype "passive"))
      (node (ref "D11") (pin "2") (pintype "passive"))
      (node (ref "VS10") (pin "1") (pintype "passive"))
      (node (ref "VS11") (pin "3") (pintype "passive"))
    )
    (net (code "15") (name "Net-(D11-Pad1)") (class "Default")
      (node (ref "D11") (pin "1") (pintype "passive"))
      (node (ref "D12") (pin "2") (pintype "passive"))
      (node (ref "VS11") (pin "1") (pintype "passive"))
      (node (ref "VS12") (pin "3") (pintype "passive"))
    )
    (net (code "16") (name "Net-(D12-Pad1)") (class "Default")
      (node (ref "D12") (pin "1") (pintype "passive"))
      (node (ref "R4") (pin "2") (pinfunction "2_2") (pintype "passive"))
      (node (ref "VS12") (pin "1") (pintype "passive"))
    )
    (net (code "17") (name "Net-(D13-Pad1)") (class "Default")
      (node (ref "D13") (pin "1") (pintype "passive"))
      (node (ref "D14") (pin "2") (pintype "passive"))
      (node (ref "VS13") (pin "1") (pintype "passive"))
      (node (ref "VS14") (pin "3") (pintype "passive"))
    )
    (net (code "18") (name "Net-(D14-Pad1)") (class "Default")
      (node (ref "D14") (pin "1") (pintype "passive"))
      (node (ref "D15") (pin "2") (pintype "passive"))
      (node (ref "VS14") (pin "1") (pintype "passive"))
      (node (ref "VS15") (pin "3") (pintype "passive"))
    )
    (net (code "19") (name "Net-(D15-Pad1)") (class "Default")
      (node (ref "D15") (pin "1") (pintype "passive"))
      (node (ref "R5") (pin "2") (pinfunction "2_2") (pintype "passive"))
      (node (ref "VS15") (pin "1") (pintype "passive"))
    )
    (net (code "20") (name "Net-(D16-Pad1)") (class "Default")
      (node (ref "D16") (pin "1") (pintype "passive"))
      (node (ref "D17") (pin "2") (pintype "passive"))
      (node (ref "VS16") (pin "1") (pintype "passive"))
      (node (ref "VS17") (pin "3") (pintype "passive"))
    )
    (net (code "21") (name "Net-(D17-Pad1)") (class "Default")
      (node (ref "D17") (pin "1") (pintype "passive"))
      (node (ref "D18") (pin "2") (pintype "passive"))
      (node (ref "VS17") (pin "1") (pintype "passive"))
      (node (ref "VS18") (pin "3") (pintype "passive"))
    )
    (net (code "22") (name "Net-(D18-Pad1)") (class "Default")
      (node (ref "D18") (pin "1") (pintype "passive"))
      (node (ref "R6") (pin "2") (pinfunction "2_2") (pintype "passive"))
      (node (ref "VS18") (pin "1") (pintype "passive"))
    )
    (net (code "23") (name "Net-(D19-Pad1)") (class "Default")
      (node (ref "D19") (pin "1") (pintype "passive"))
      (node (ref "D20") (pin "2") (pintype "passive"))
      (node (ref "VS19") (pin "1") (pintype "passive"))
      (node (ref "VS20") (pin "3") (pintype "passive"))
    )
    (net (code "24") (name "Net-(D20-Pad1)") (class "Default")
      (node (ref "D20") (pin "1") (pintype "passive"))
      (node (ref "D21") (pin "2") (pintype "passive"))
      (node (ref "VS20") (pin "1") (pintype "passive"))
      (node (ref "VS21") (pin "3") (pintype "passive"))
    )
    (net (code "25") (name "Net-(D21-Pad1)") (class "Default")
      (node (ref "D21") (pin "1") (pintype "passive"))
      (node (ref "R7") (pin "2") (pinfunction "2_2") (pintype "passive"))
      (node (ref "VS21") (pin "1") (pintype "passive"))
    )
    (net (code "26") (name "Net-(D22-Pad1)") (class "Default")
      (node (ref "D22") (pin "1") (pintype "passive"))
      (node (ref "D23") (pin "2") (pintype "passive"))
      (node (ref "VS22") (pin "1") (pintype "passive"))
      (node (ref "VS23") (pin "3") (pintype "passive"))
    )
    (net (code "27") (name "Net-(D23-Pad1)") (class "Default")
      (node (ref "D23") (pin "1") (pintype "passive"))
      (node (ref "D24") (pin "2") (pintype "passive"))
      (node (ref "VS23") (pin "1") (pintype "passive"))
      (node (ref "VS24") (pin "3") (pintype "passive"))
    )
    (net (code "28") (name "Net-(D24-Pad1)") (class "Default")
      (node (ref "D24") (pin "1") (pintype "passive"))
      (node (ref "R8") (pin "2") (pinfunction "2_2") (pintype "passive"))
      (node (ref "VS24") (pin "1") (pintype "passive"))
    )
    (net (code "29") (name "Net-(D25-Pad1)") (class "Default")
      (node (ref "D25") (pin "1") (pintype "passive"))
      (node (ref "D26") (pin "2") (pintype "passive"))
      (node (ref "VS25") (pin "1") (pintype "passive"))
      (node (ref "VS26") (pin "3") (pintype "passive"))
    )
    (net (code "30") (name "Net-(D26-Pad1)") (class "Default")
      (node (ref "D26") (pin "1") (pintype "passive"))
      (node (ref "D27") (pin "2") (pintype "passive"))
      (node (ref "VS26") (pin "1") (pintype "passive"))
      (node (ref "VS27") (pin "3") (pintype "passive"))
    )
    (net (code "31") (name "Net-(D27-Pad1)") (class "Default")
      (node (ref "D27") (pin "1") (pintype "passive"))
      (node (ref "R9") (pin "2") (pinfunction "2_2") (pintype "passive"))
      (node (ref "VS27") (pin "1") (pintype "passive"))
    )
    (net (code "32") (name "Net-(D28-Pad1)") (class "Default")
      (node (ref "D28") (pin "1") (pintype "passive"))
      (node (ref "D29") (pin "2") (pintype "passive"))
      (node (ref "VS28") (pin "1") (pintype "passive"))
      (node (ref "VS29") (pin "3") (pintype "passive"))
    )
    (net (code "33") (name "Net-(D29-Pad1)") (class "Default")
      (node (ref "D29") (pin "1") (pintype "passive"))
      (node (ref "D30") (pin "2") (pintype "passive"))
      (node (ref "VS29") (pin "1") (pintype "passive"))
      (node (ref "VS30") (pin "3") (pintype "passive"))
    )
    (net (code "34") (name "Net-(D30-Pad1)") (class "Default")
      (node (ref "D30") (pin "1") (pintype "passive"))
      (node (ref "R10") (pin "2") (pinfunction "2_2") (pintype "passive"))
      (node (ref "VS30") (pin "1") (pintype "passive"))
    )
    (net (code "35") (name "Net-(D31-Pad1)") (class "Default")
      (node (ref "D31") (pin "1") (pintype "passive"))
      (node (ref "D32") (pin "2") (pintype "passive"))
      (node (ref "VS31") (pin "1") (pintype "passive"))
      (node (ref "VS32") (pin "3") (pintype "passive"))
    )
    (net (code "36") (name "Net-(D32-Pad1)") (class "Default")
      (node (ref "D32") (pin "1") (pintype "passive"))
      (node (ref "D33") (pin "2") (pintype "passive"))
      (node (ref "VS32") (pin "1") (pintype "passive"))
      (node (ref "VS33") (pin "3") (pintype "passive"))
    )
    (net (code "37") (name "Net-(D33-Pad1)") (class "Default")
      (node (ref "D33") (pin "1") (pintype "passive"))
      (node (ref "R11") (pin "2") (pinfunction "2_2") (pintype "passive"))
      (node (ref "VS33") (pin "1") (pintype "passive"))
    )
    (net (code "38") (name "Net-(D34-Pad1)") (class "Default")
      (node (ref "D34") (pin "1") (pintype "passive"))
      (node (ref "D35") (pin "2") (pintype "passive"))
      (node (ref "VS34") (pin "1") (pintype "passive"))
      (node (ref "VS35") (pin "3") (pintype "passive"))
    )
    (net (code "39") (name "Net-(D35-Pad1)") (class "Default")
      (node (ref "D35") (pin "1") (pintype "passive"))
      (node (ref "D36") (pin "2") (pintype "passive"))
      (node (ref "VS35") (pin "1") (pintype "passive"))
      (node (ref "VS36") (pin "3") (pintype "passive"))
    )
    (net (code "40") (name "Net-(D36-Pad1)") (class "Default")
      (node (ref "D36") (pin "1") (pintype "passive"))
      (node (ref "R12") (pin "2") (pinfunction "2_2") (pintype "passive"))
      (node (ref "VS36") (pin "1") (pintype "passive"))
    )
    (net (code "41") (name "Net-(D37-Pad1)") (class "Default")
      (node (ref "D37") (pin "1") (pintype "passive"))
      (node (ref "D38") (pin "2") (pintype "passive"))
      (node (ref "VS37") (pin "1") (pintype "passive"))
      (node (ref "VS38") (pin "3") (pintype "passive"))
    )
    (net (code "42") (name "Net-(D38-Pad1)") (class "Default")
      (node (ref "D38") (pin "1") (pintype "passive"))
      (node (ref "D39") (pin "2") (pintype "passive"))
      (node (ref "VS38") (pin "1") (pintype "passive"))
      (node (ref "VS39") (pin "3") (pintype "passive"))
    )
    (net (code "43") (name "Net-(D39-Pad1)") (class "Default")
      (node (ref "D39") (pin "1") (pintype "passive"))
      (node (ref "R13") (pin "2") (pinfunction "2_2") (pintype "passive"))
      (node (ref "VS39") (pin "1") (pintype "passive"))
    )
    (net (code "44") (name "Net-(D40-Pad1)") (class "Default")
      (node (ref "D40") (pin "1") (pintype "passive"))
      (node (ref "D41") (pin "2") (pintype "passive"))
      (node (ref "VS40") (pin "1") (pintype "passive"))
      (node (ref "VS41") (pin "3") (pintype "passive"))
    )
    (net (code "45") (name "Net-(D41-Pad1)") (class "Default")
      (node (ref "D41") (pin "1") (pintype "passive"))
      (node (ref "D42") (pin "2") (pintype "passive"))
      (node (ref "VS41") (pin "1") (pintype "passive"))
      (node (ref "VS42") (pin "3") (pintype "passive"))
    )
    (net (code "46") (name "Net-(D42-Pad1)") (class "Default")
      (node (ref "D42") (pin "1") (pintype "passive"))
      (node (ref "R14") (pin "2") (pinfunction "2_2") (pintype "passive"))
      (node (ref "VS42") (pin "1") (pintype "passive"))
    )
    (net (code "47") (name "Net-(D43-Pad1)") (class "Default")
      (node (ref "D43") (pin "1") (pintype "passive"))
      (node (ref "D44") (pin "2") (pintype "passive"))
      (node (ref "VS43") (pin "1") (pintype "passive"))
      (node (ref "VS44") (pin "3") (pintype "passive"))
    )
    (net (code "48") (name "Net-(D44-Pad1)") (class "Default")
      (node (ref "D44") (pin "1") (pintype "passive"))
      (node (ref "D45") (pin "2") (pintype "passive"))
      (node (ref "VS44") (pin "1") (pintype "passive"))
      (node (ref "VS45") (pin "3") (pintype "passive"))
    )
    (net (code "49") (name "Net-(D45-Pad1)") (class "Default")
      (node (ref "D45") (pin "1") (pintype "passive"))
      (node (ref "R15") (pin "2") (pinfunction "2_2") (pintype "passive"))
      (node (ref "VS45") (pin "1") (pintype "passive"))
    )
    (net (code "50") (name "Net-(D46-Pad1)") (class "Default")
      (node (ref "D46") (pin "1") (pintype "passive"))
      (node (ref "D47") (pin "2") (pintype "passive"))
      (node (ref "VS46") (pin "1") (pintype "passive"))
      (node (ref "VS47") (pin "3") (pintype "passive"))
    )
    (net (code "51") (name "Net-(D47-Pad1)") (class "Default")
      (node (ref "D47") (pin "1") (pintype "passive"))
      (node (ref "D48") (pin "2") (pintype "passive"))
      (node (ref "VS47") (pin "1") (pintype "passive"))
      (node (ref "VS48") (pin "3") (pintype "passive"))
    )
    (net (code "52") (name "Net-(D48-Pad1)") (class "Default")
      (node (ref "D48") (pin "1") (pintype "passive"))
      (node (ref "R16") (pin "2") (pinfunction "2_2") (pintype "passive"))
      (node (ref "VS48") (pin "1") (pintype "passive"))
    )
    (net (code "53") (name "Net-(D49-Pad1)") (class "Default")
      (node (ref "D49") (pin "1") (pintype "passive"))
      (node (ref "D50") (pin "2") (pintype "passive"))
      (node (ref "VS49") (pin "1") (pintype "passive"))
      (node (ref "VS50") (pin "3") (pintype "passive"))
    )
    (net (code "54") (name "Net-(D50-Pad1)") (class "Default")
      (node (ref "D50") (pin "1") (pintype "passive"))
      (node (ref "D51") (pin "2") (pintype "passive"))
      (node (ref "VS50") (pin "1") (pintype "passive"))
      (node (ref "VS51") (pin "3") (pintype "passive"))
    )
    (net (code "55") (name "Net-(D51-Pad1)") (class "Default")
      (node (ref "D51") (pin "1") (pintype "passive"))
      (node (ref "R17") (pin "2") (pinfunction "2_2") (pintype "passive"))
      (node (ref "VS51") (pin "1") (pintype "passive"))
    )
    (net (code "56") (name "Net-(D52-Pad1)") (class "Default")
      (node (ref "D52") (pin "1") (pintype "passive"))
      (node (ref "D53") (pin "2") (pintype "passive"))
      (node (ref "VS52") (pin "1") (pintype "passive"))
      (node (ref "VS53") (pin "3") (pintype "passive"))
    )
    (net (code "57") (name "Net-(D53-Pad1)") (class "Default")
      (node (ref "D53") (pin "1") (pintype "passive"))
      (node (ref "D54") (pin "2") (pintype "passive"))
      (node (ref "VS53") (pin "1") (pintype "passive"))
      (node (ref "VS54") (pin "3") (pintype "passive"))
    )
    (net (code "58") (name "Net-(D54-Pad1)") (class "Default")
      (node (ref "D54") (pin "1") (pintype "passive"))
      (node (ref "R18") (pin "2") (pinfunction "2_2") (pintype "passive"))
      (node (ref "VS54") (pin "1") (pintype "passive"))
    )
    (net (code "59") (name "Net-(D55-Pad1)") (class "Default")
      (node (ref "D55") (pin "1") (pintype "passive"))
      (node (ref "D56") (pin "2") (pintype "passive"))
      (node (ref "VS55") (pin "1") (pintype "passive"))
      (node (ref "VS56") (pin "3") (pintype "passive"))
    )
    (net (code "60") (name "Net-(D56-Pad1)") (class "Default")
      (node (ref "D56") (pin "1") (pintype "passive"))
      (node (ref "D57") (pin "2") (pintype "passive"))
      (node (ref "VS56") (pin "1") (pintype "passive"))
      (node (ref "VS57") (pin "3") (pintype "passive"))
    )
    (net (code "61") (name "Net-(D57-Pad1)") (class "Default")
      (node (ref "D57") (pin "1") (pintype "passive"))
      (node (ref "R19") (pin "2") (pinfunction "2_2") (pintype "passive"))
      (node (ref "VS57") (pin "1") (pintype "passive"))
    )
    (net (code "62") (name "Net-(D58-Pad1)") (class "Default")
      (node (ref "D58") (pin "1") (pintype "passive"))
      (node (ref "D59") (pin "2") (pintype "passive"))
      (node (ref "VS58") (pin "1") (pintype "passive"))
      (node (ref "VS59") (pin "3") (pintype "passive"))
    )
    (net (code "63") (name "Net-(D59-Pad1)") (class "Default")
      (node (ref "D59") (pin "1") (pintype "passive"))
      (node (ref "D60") (pin "2") (pintype "passive"))
      (node (ref "VS59") (pin "1") (pintype "passive"))
      (node (ref "VS60") (pin "3") (pintype "passive"))
    )
    (net (code "64") (name "Net-(D60-Pad1)") (class "Default")
      (node (ref "D60") (pin "1") (pintype "passive"))
      (node (ref "R20") (pin "2") (pinfunction "2_2") (pintype "passive"))
      (node (ref "VS60") (pin "1") (pintype "passive"))
    )
    (net (code "65") (name "Net-(D61-Pad1)") (class "Default")
      (node (ref "D61") (pin "1") (pintype "passive"))
      (node (ref "D62") (pin "2") (pintype "passive"))
      (node (ref "VS61") (pin "1") (pintype "passive"))
      (node (ref "VS62") (pin "3") (pintype "passive"))
    )
    (net (code "66") (name "Net-(D62-Pad1)") (class "Default")
      (node (ref "D62") (pin "1") (pintype "passive"))
      (node (ref "D63") (pin "2") (pintype "passive"))
      (node (ref "VS62") (pin "1") (pintype "passive"))
      (node (ref "VS63") (pin "3") (pintype "passive"))
    )
    (net (code "67") (name "Net-(D63-Pad1)") (class "Default")
      (node (ref "D63") (pin "1") (pintype "passive"))
      (node (ref "R21") (pin "2") (pinfunction "2_2") (pintype "passive"))
      (node (ref "VS63") (pin "1") (pintype "passive"))
    )
    (net (code "68") (name "Net-(D64-Pad1)") (class "Default")
      (node (ref "D64") (pin "1") (pintype "passive"))
      (node (ref "D65") (pin "2") (pintype "passive"))
      (node (ref "VS64") (pin "1") (pintype "passive"))
      (node (ref "VS65") (pin "3") (pintype "passive"))
    )
    (net (code "69") (name "Net-(D65-Pad1)") (class "Default")
      (node (ref "D65") (pin "1") (pintype "passive"))
      (node (ref "D66") (pin "2") (pintype "passive"))
      (node (ref "VS65") (pin "1") (pintype "passive"))
      (node (ref "VS66") (pin "3") (pintype "passive"))
    )
    (net (code "70") (name "Net-(D66-Pad1)") (class "Default")
      (node (ref "D66") (pin "1") (pintype "passive"))
      (node (ref "R22") (pin "2") (pinfunction "2_2") (pintype "passive"))
      (node (ref "VS66") (pin "1") (pintype "passive"))
    )
    (net (code "71") (name "Net-(D67-Pad1)") (class "Default")
      (node (ref "D67") (pin "1") (pintype "passive"))
      (node (ref "D68") (pin "2") (pintype "passive"))
      (node (ref "VS67") (pin "1") (pintype "passive"))
      (node (ref "VS68") (pin "3") (pintype "passive"))
    )
    (net (code "72") (name "Net-(D68-Pad1)") (class "Default")
      (node (ref "D68") (pin "1") (pintype "passive"))
      (node (ref "R23") (pin "2") (pinfunction "2_2") (pintype "passive"))
      (node (ref "VS68") (pin "1") (pintype "passive"))
    )
    (net (code "73") (name "Net-(R23-Pad1)") (class "Default")
      (node (ref "R23") (pin "1") (pinfunction "1_1") (pintype "passive"))
      (node (ref "R24") (pin "2") (pinfunction "2_2") (pintype "passive"))
    )
    (net (code "74") (name "unconnected-(ST1-Pad5)") (class "Default")
      (node (ref "ST1") (pin "5") (pintype "passive"))
    )
    (net (code "75") (name "unconnected-(ST1-Pad6)") (class "Default")
      (node (ref "ST1") (pin "6") (pintype "passive"))
    )
    (net (code "76") (name "unconnected-(ST1-Pad7)") (class "Default")
      (node (ref "ST1") (pin "7") (pintype "passive"))
    )
    (net (code "77") (name "unconnected-(ST1-Pad8)") (class "Default")
      (node (ref "ST1") (pin "8") (pintype "passive"))
    )
    (net (code "78") (name "unconnected-(VS1-Pad2)") (class "Default")
      (node (ref "VS1") (pin "2") (pintype "passive"))
    )
    (net (code "79") (name "unconnected-(VS2-Pad2)") (class "Default")
      (node (ref "VS2") (pin "2") (pintype "passive"))
    )
    (net (code "80") (name "unconnected-(VS3-Pad2)") (class "Default")
      (node (ref "VS3") (pin "2") (pintype "passive"))
    )
    (net (code "81") (name "unconnected-(VS4-Pad2)") (class "Default")
      (node (ref "VS4") (pin "2") (pintype "passive"))
    )
    (net (code "82") (name "unconnected-(VS5-Pad2)") (class "Default")
      (node (ref "VS5") (pin "2") (pintype "passive"))
    )
    (net (code "83") (name "unconnected-(VS6-Pad2)") (class "Default")
      (node (ref "VS6") (pin "2") (pintype "passive"))
    )
    (net (code "84") (name "unconnected-(VS7-Pad2)") (class "Default")
      (node (ref "VS7") (pin "2") (pintype "passive"))
    )
    (net (code "85") (name "unconnected-(VS8-Pad2)") (class "Default")
      (node (ref "VS8") (pin "2") (pintype "passive"))
    )
    (net (code "86") (name "unconnected-(VS9-Pad2)") (class "Default")
      (node (ref "VS9") (pin "2") (pintype "passive"))
    )
    (net (code "87") (name "unconnected-(VS10-Pad2)") (class "Default")
      (node (ref "VS10") (pin "2") (pintype "passive"))
    )
    (net (code "88") (name "unconnected-(VS11-Pad2)") (class "Default")
      (node (ref "VS11") (pin "2") (pintype "passive"))
    )
    (net (code "89") (name "unconnected-(VS12-Pad2)") (class "Default")
      (node (ref "VS12") (pin "2") (pintype "passive"))
    )
    (net (code "90") (name "unconnected-(VS13-Pad2)") (class "Default")
      (node (ref "VS13") (pin "2") (pintype "passive"))
    )
    (net (code "91") (name "unconnected-(VS14-Pad2)") (class "Default")
      (node (ref "VS14") (pin "2") (pintype "passive"))
    )
    (net (code "92") (name "unconnected-(VS15-Pad2)") (class "Default")
      (node (ref "VS15") (pin "2") (pintype "passive"))
    )
    (net (code "93") (name "unconnected-(VS16-Pad2)") (class "Default")
      (node (ref "VS16") (pin "2") (pintype "passive"))
    )
    (net (code "94") (name "unconnected-(VS17-Pad2)") (class "Default")
      (node (ref "VS17") (pin "2") (pintype "passive"))
    )
    (net (code "95") (name "unconnected-(VS18-Pad2)") (class "Default")
      (node (ref "VS18") (pin "2") (pintype "passive"))
    )
    (net (code "96") (name "unconnected-(VS19-Pad2)") (class "Default")
      (node (ref "VS19") (pin "2") (pintype "passive"))
    )
    (net (code "97") (name "unconnected-(VS20-Pad2)") (class "Default")
      (node (ref "VS20") (pin "2") (pintype "passive"))
    )
    (net (code "98") (name "unconnected-(VS21-Pad2)") (class "Default")
      (node (ref "VS21") (pin "2") (pintype "passive"))
    )
    (net (code "99") (name "unconnected-(VS22-Pad2)") (class "Default")
      (node (ref "VS22") (pin "2") (pintype "passive"))
    )
    (net (code "100") (name "unconnected-(VS23-Pad2)") (class "Default")
      (node (ref "VS23") (pin "2") (pintype "passive"))
    )
    (net (code "101") (name "unconnected-(VS24-Pad2)") (class "Default")
      (node (ref "VS24") (pin "2") (pintype "passive"))
    )
    (net (code "102") (name "unconnected-(VS25-Pad2)") (class "Default")
      (node (ref "VS25") (pin "2") (pintype "passive"))
    )
    (net (code "103") (name "unconnected-(VS26-Pad2)") (class "Default")
      (node (ref "VS26") (pin "2") (pintype "passive"))
    )
    (net (code "104") (name "unconnected-(VS27-Pad2)") (class "Default")
      (node (ref "VS27") (pin "2") (pintype "passive"))
    )
    (net (code "105") (name "unconnected-(VS28-Pad2)") (class "Default")
      (node (ref "VS28") (pin "2") (pintype "passive"))
    )
    (net (code "106") (name "unconnected-(VS29-Pad2)") (class "Default")
      (node (ref "VS29") (pin "2") (pintype "passive"))
    )
    (net (code "107") (name "unconnected-(VS30-Pad2)") (class "Default")
      (node (ref "VS30") (pin "2") (pintype "passive"))
    )
    (net (code "108") (name "unconnected-(VS31-Pad2)") (class "Default")
      (node (ref "VS31") (pin "2") (pintype "passive"))
    )
    (net (code "109") (name "unconnected-(VS32-Pad2)") (class "Default")
      (node (ref "VS32") (pin "2") (pintype "passive"))
    )
    (net (code "110") (name "unconnected-(VS33-Pad2)") (class "Default")
      (node (ref "VS33") (pin "2") (pintype "passive"))
    )
    (net (code "111") (name "unconnected-(VS34-Pad2)") (class "Default")
      (node (ref "VS34") (pin "2") (pintype "passive"))
    )
    (net (code "112") (name "unconnected-(VS35-Pad2)") (class "Default")
      (node (ref "VS35") (pin "2") (pintype "passive"))
    )
    (net (code "113") (name "unconnected-(VS36-Pad2)") (class "Default")
      (node (ref "VS36") (pin "2") (pintype "passive"))
    )
    (net (code "114") (name "unconnected-(VS37-Pad2)") (class "Default")
      (node (ref "VS37") (pin "2") (pintype "passive"))
    )
    (net (code "115") (name "unconnected-(VS38-Pad2)") (class "Default")
      (node (ref "VS38") (pin "2") (pintype "passive"))
    )
    (net (code "116") (name "unconnected-(VS39-Pad2)") (class "Default")
      (node (ref "VS39") (pin "2") (pintype "passive"))
    )
    (net (code "117") (name "unconnected-(VS40-Pad2)") (class "Default")
      (node (ref "VS40") (pin "2") (pintype "passive"))
    )
    (net (code "118") (name "unconnected-(VS41-Pad2)") (class "Default")
      (node (ref "VS41") (pin "2") (pintype "passive"))
    )
    (net (code "119") (name "unconnected-(VS42-Pad2)") (class "Default")
      (node (ref "VS42") (pin "2") (pintype "passive"))
    )
    (net (code "120") (name "unconnected-(VS43-Pad2)") (class "Default")
      (node (ref "VS43") (pin "2") (pintype "passive"))
    )
    (net (code "121") (name "unconnected-(VS44-Pad2)") (class "Default")
      (node (ref "VS44") (pin "2") (pintype "passive"))
    )
    (net (code "122") (name "unconnected-(VS45-Pad2)") (class "Default")
      (node (ref "VS45") (pin "2") (pintype "passive"))
    )
    (net (code "123") (name "unconnected-(VS46-Pad2)") (class "Default")
      (node (ref "VS46") (pin "2") (pintype "passive"))
    )
    (net (code "124") (name "unconnected-(VS47-Pad2)") (class "Default")
      (node (ref "VS47") (pin "2") (pintype "passive"))
    )
    (net (code "125") (name "unconnected-(VS48-Pad2)") (class "Default")
      (node (ref "VS48") (pin "2") (pintype "passive"))
    )
    (net (code "126") (name "unconnected-(VS49-Pad2)") (class "Default")
      (node (ref "VS49") (pin "2") (pintype "passive"))
    )
    (net (code "127") (name "unconnected-(VS50-Pad2)") (class "Default")
      (node (ref "VS50") (pin "2") (pintype "passive"))
    )
    (net (code "128") (name "unconnected-(VS51-Pad2)") (class "Default")
      (node (ref "VS51") (pin "2") (pintype "passive"))
    )
    (net (code "129") (name "unconnected-(VS52-Pad2)") (class "Default")
      (node (ref "VS52") (pin "2") (pintype "passive"))
    )
    (net (code "130") (name "unconnected-(VS53-Pad2)") (class "Default")
      (node (ref "VS53") (pin "2") (pintype "passive"))
    )
    (net (code "131") (name "unconnected-(VS54-Pad2)") (class "Default")
      (node (ref "VS54") (pin "2") (pintype "passive"))
    )
    (net (code "132") (name "unconnected-(VS55-Pad2)") (class "Default")
      (node (ref "VS55") (pin "2") (pintype "passive"))
    )
    (net (code "133") (name "unconnected-(VS56-Pad2)") (class "Default")
      (node (ref "VS56") (pin "2") (pintype "passive"))
    )
    (net (code "134") (name "unconnected-(VS57-Pad2)") (class "Default")
      (node (ref "VS57") (pin "2") (pintype "passive"))
    )
    (net (code "135") (name "unconnected-(VS58-Pad2)") (class "Default")
      (node (ref "VS58") (pin "2") (pintype "passive"))
    )
    (net (code "136") (name "unconnected-(VS59-Pad2)") (class "Default")
      (node (ref "VS59") (pin "2") (pintype "passive"))
    )
    (net (code "137") (name "unconnected-(VS60-Pad2)") (class "Default")
      (node (ref "VS60") (pin "2") (pintype "passive"))
    )
    (net (code "138") (name "unconnected-(VS61-Pad2)") (class "Default")
      (node (ref "VS61") (pin "2") (pintype "passive"))
    )
    (net (code "139") (name "unconnected-(VS62-Pad2)") (class "Default")
      (node (ref "VS62") (pin "2") (pintype "passive"))
    )
    (net (code "140") (name "unconnected-(VS63-Pad2)") (class "Default")
      (node (ref "VS63") (pin "2") (pintype "passive"))
    )
    (net (code "141") (name "unconnected-(VS64-Pad2)") (class "Default")
      (node (ref "VS64") (pin "2") (pintype "passive"))
    )
    (net (code "142") (name "unconnected-(VS65-Pad2)") (class "Default")
      (node (ref "VS65") (pin "2") (pintype "passive"))
    )
    (net (code "143") (name "unconnected-(VS66-Pad2)") (class "Default")
      (node (ref "VS66") (pin "2") (pintype "passive"))
    )
    (net (code "144") (name "unconnected-(VS67-Pad2)") (class "Default")
      (node (ref "VS67") (pin "2") (pintype "passive"))
    )
    (net (code "145") (name "unconnected-(VS68-Pad2)") (class "Default")
      (node (ref "VS68") (pin "2") (pintype "passive"))
    )
  )
)
